# 1_P1.net
KiCad netlist of a schematic drawn in Altium Designer
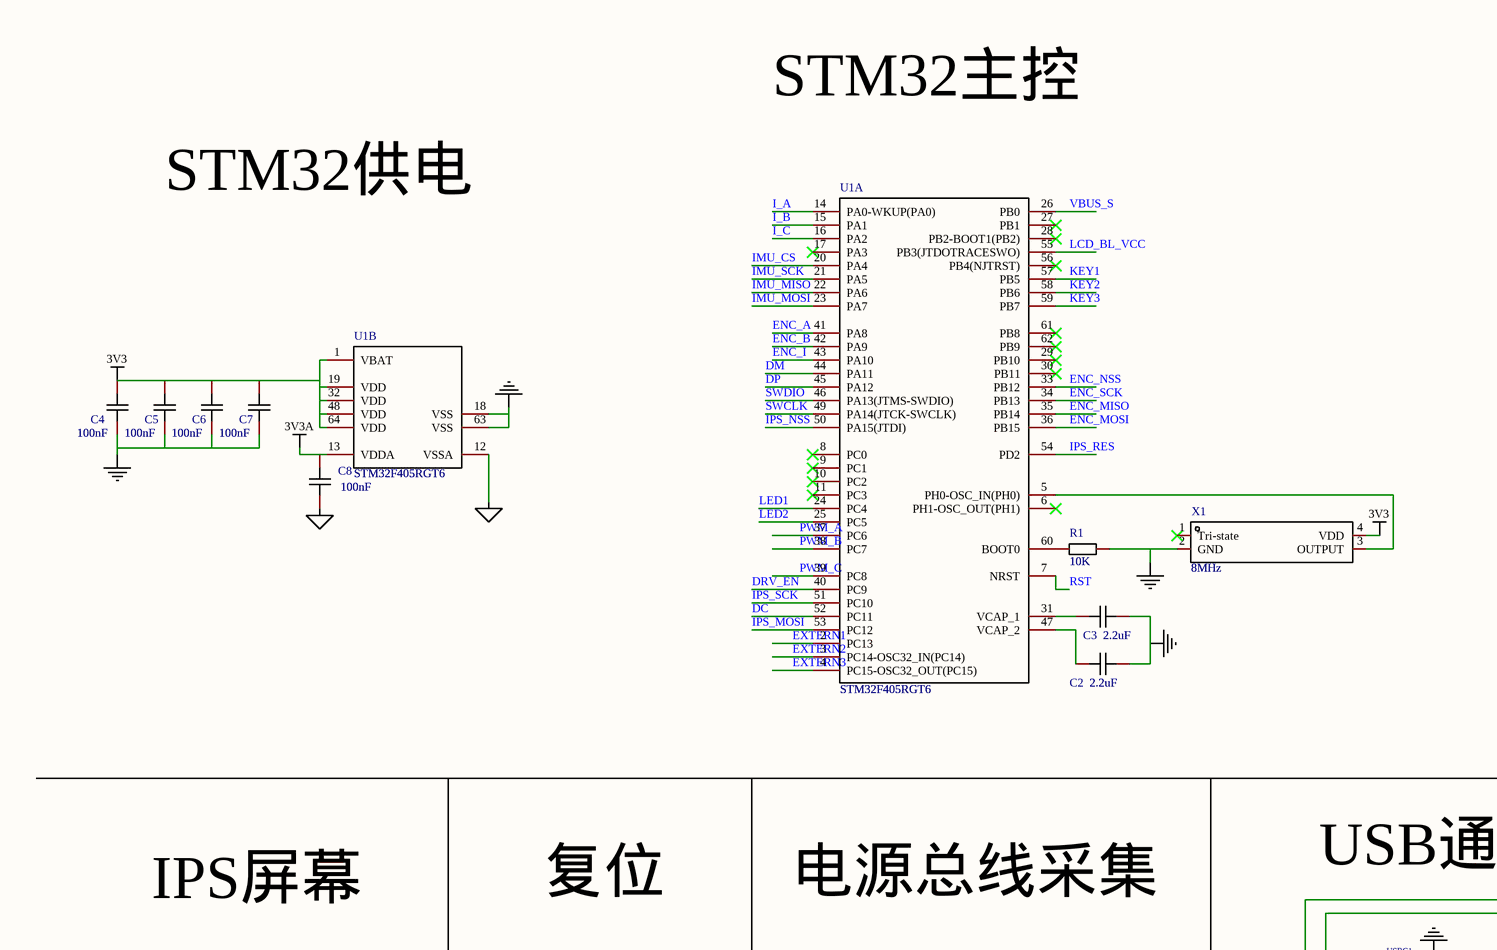
[diagram p0: 1_P1.schdoc, top left]
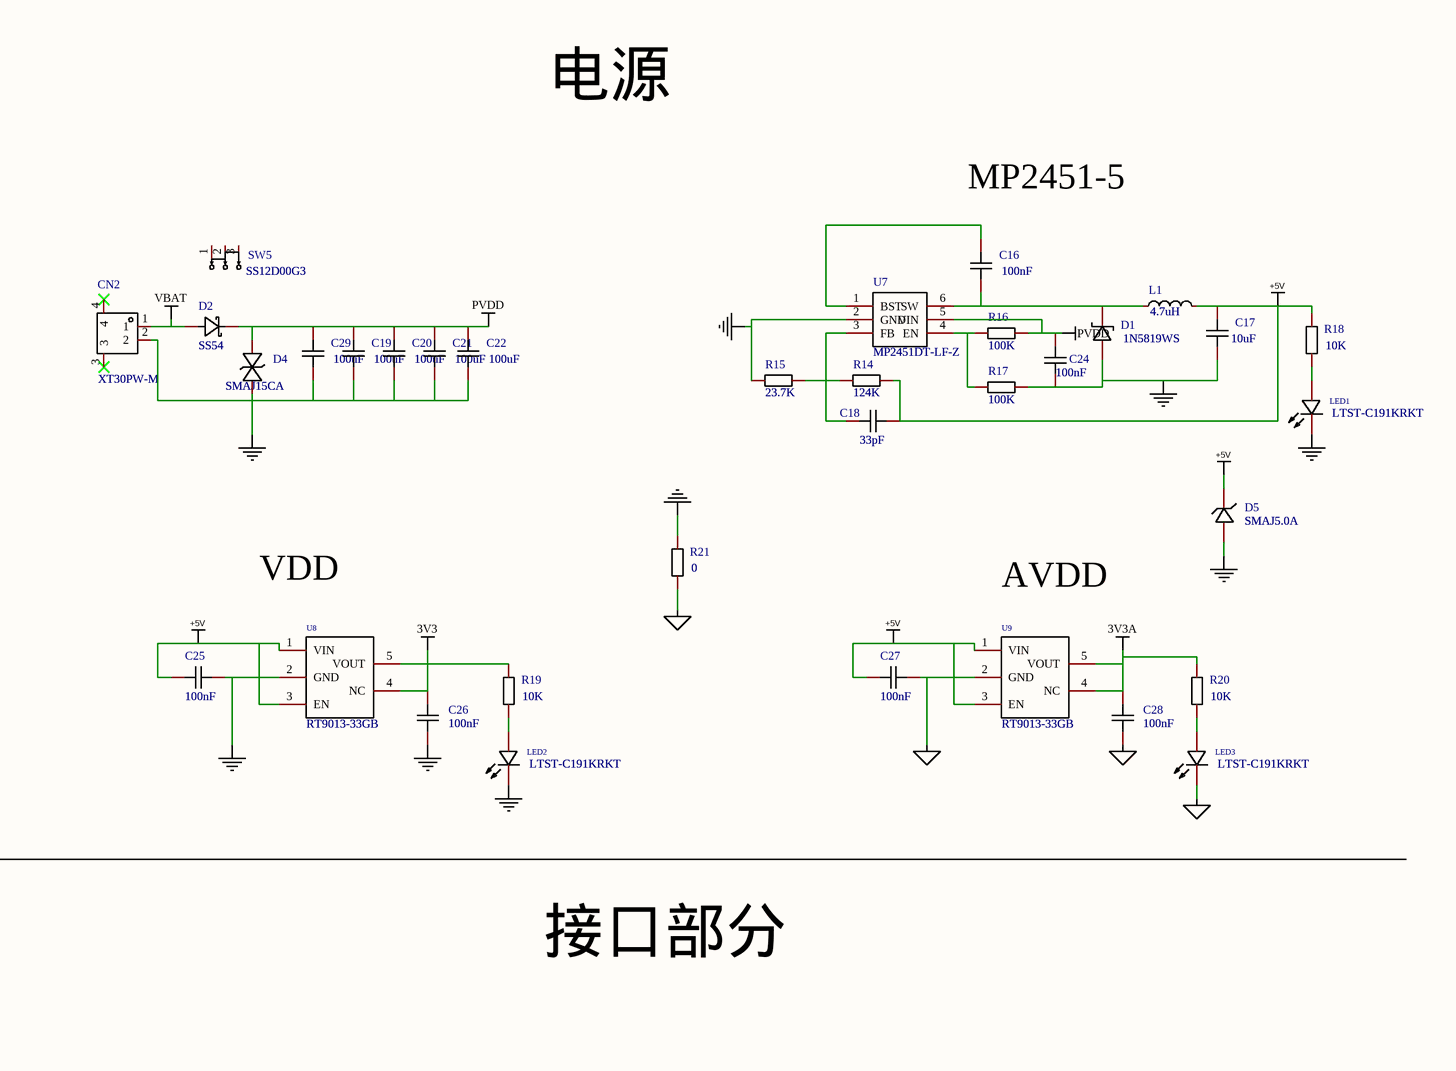
[diagram p1: 1_P1.schdoc, top right]
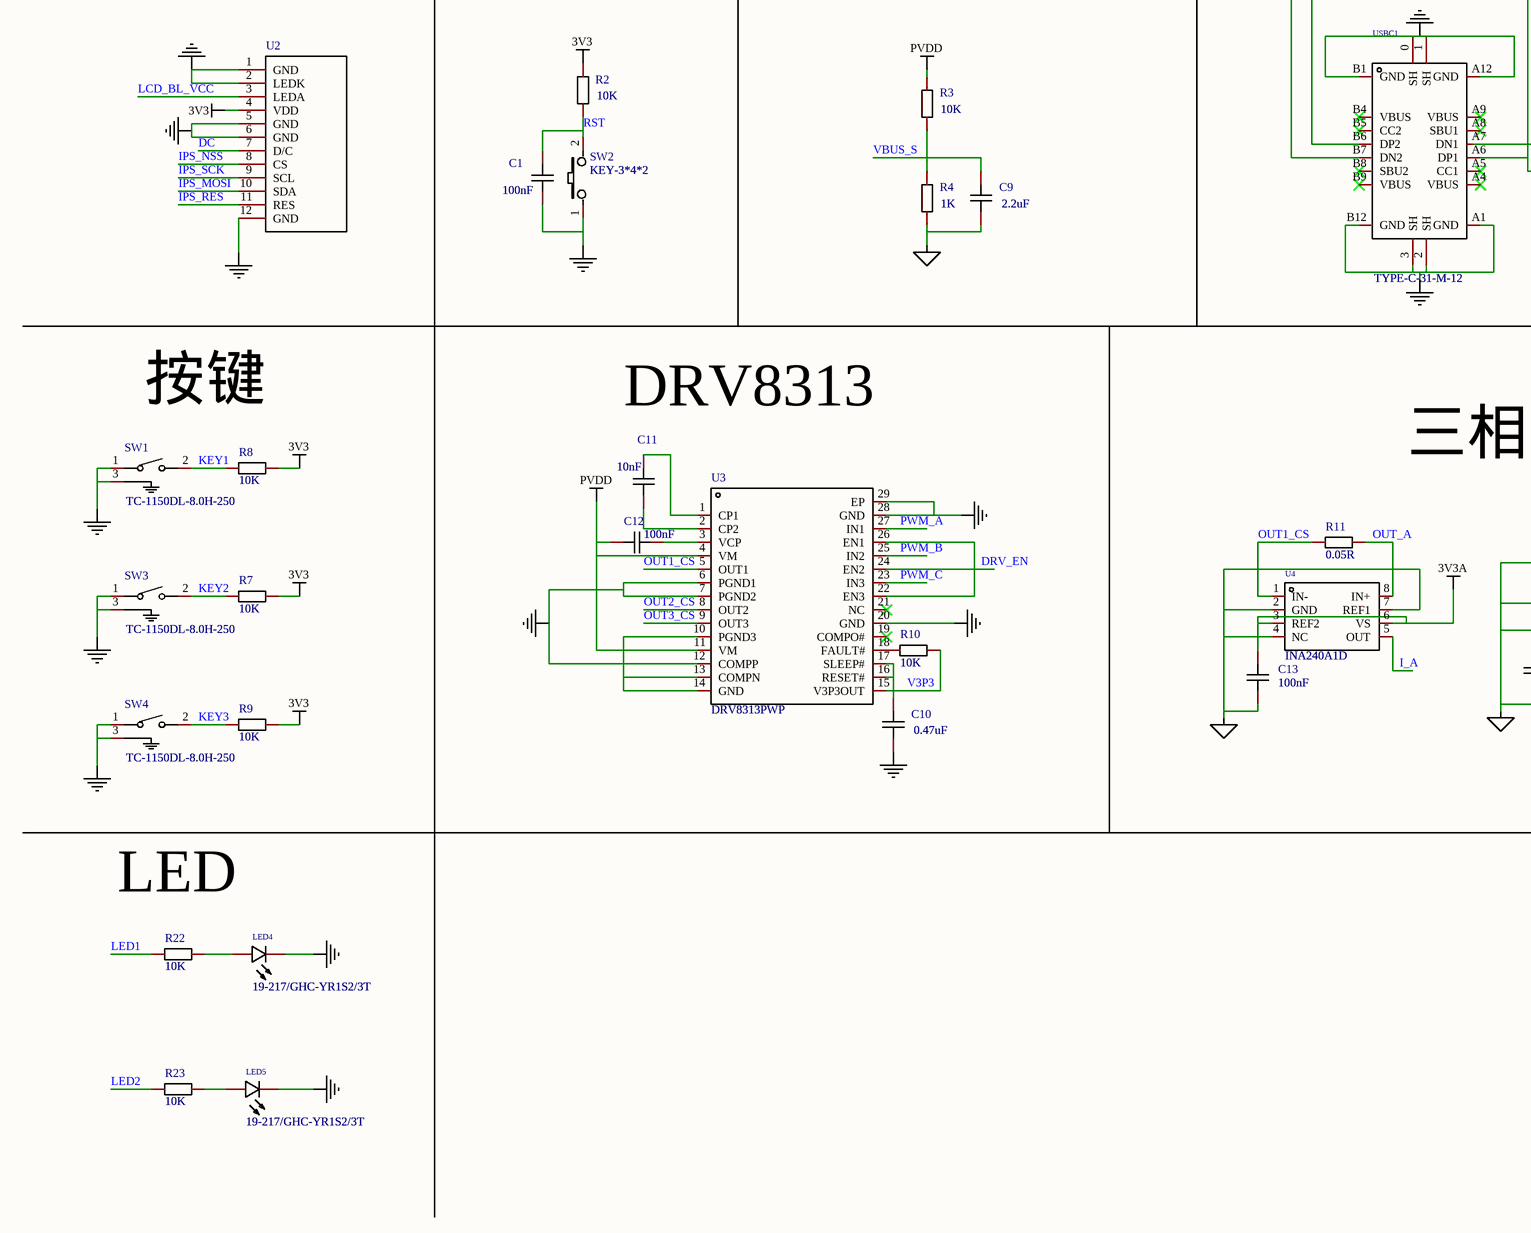
[diagram p2: 1_P1.schdoc, bottom left]
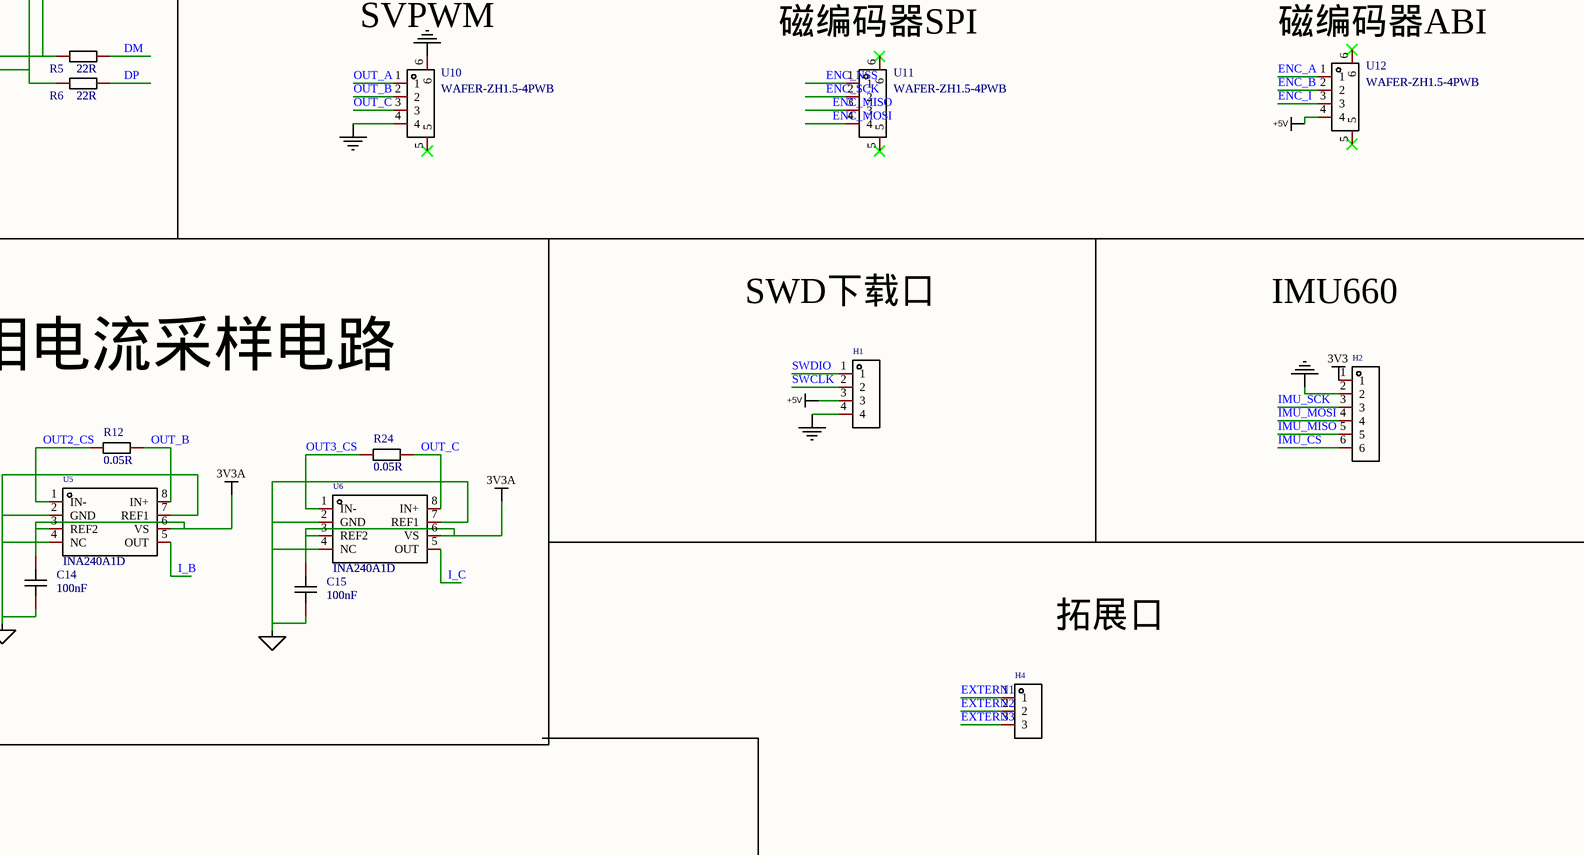
[diagram p3: 1_P1.schdoc, bottom right]

(export (version "E")
  (design (tool "Eeschema 10.0.6"))
  (components
    (comp (ref "C1")
      (value "100nF")
      (fields (field (name "NAME") "100nF"))
      (libsource (lib "altium-import") (part "root_1_CAP_0603_"))
    )
    (comp (ref "C2")
      (value "2.2uF")
      (fields (field (name "NAME") "2.2uF"))
      (libsource (lib "altium-import") (part "root_0_CAP_0603_"))
    )
    (comp (ref "C3")
      (value "2.2uF")
      (fields (field (name "NAME") "2.2uF"))
      (libsource (lib "altium-import") (part "root_0_CAP_0603_"))
    )
    (comp (ref "C4")
      (value "100nF")
      (fields (field (name "NAME") "100nF"))
      (libsource (lib "altium-import") (part "root_1_CAP_0603_"))
    )
    (comp (ref "C5")
      (value "100nF")
      (fields (field (name "NAME") "100nF"))
      (libsource (lib "altium-import") (part "root_1_CAP_0603_"))
    )
    (comp (ref "C6")
      (value "100nF")
      (fields (field (name "NAME") "100nF"))
      (libsource (lib "altium-import") (part "root_1_CAP_0603_"))
    )
    (comp (ref "C7")
      (value "100nF")
      (fields (field (name "NAME") "100nF"))
      (libsource (lib "altium-import") (part "root_1_CAP_0603_"))
    )
    (comp (ref "C8")
      (value "100nF")
      (fields (field (name "NAME") "100nF"))
      (libsource (lib "altium-import") (part "root_1_CAP_0603_"))
    )
    (comp (ref "C9")
      (value "2.2uF")
      (fields (field (name "NAME") "2.2uF"))
      (libsource (lib "altium-import") (part "root_1_CAP_0603_"))
    )
    (comp (ref "C10")
      (value "0.47uF")
      (fields (field (name "NAME") "0.47uF"))
      (libsource (lib "altium-import") (part "root_1_CAP_0603_"))
    )
    (comp (ref "C11")
      (value "10nF")
      (fields (field (name "NAME") "10nF"))
      (libsource (lib "altium-import") (part "root_1_CAP_0603_"))
    )
    (comp (ref "C12")
      (value "100nF")
      (fields (field (name "NAME") "100nF"))
      (libsource (lib "altium-import") (part "root_0_CAP_0603_"))
    )
    (comp (ref "C13")
      (value "100nF")
      (fields (field (name "NAME") "100nF"))
      (libsource (lib "altium-import") (part "root_1_CAP_0603_"))
    )
    (comp (ref "C14")
      (value "100nF")
      (fields (field (name "NAME") "100nF"))
      (libsource (lib "altium-import") (part "root_1_CAP_0603_"))
    )
    (comp (ref "C15")
      (value "100nF")
      (fields (field (name "NAME") "100nF"))
      (libsource (lib "altium-import") (part "root_1_CAP_0603_"))
    )
    (comp (ref "C16")
      (value "100nF")
      (fields (field (name "NAME") "100nF"))
      (libsource (lib "altium-import") (part "root_1_CAP_0603_"))
    )
    (comp (ref "C17")
      (value "10uF")
      (fields (field (name "NAME") "10uF"))
      (libsource (lib "altium-import") (part "root_1_CAP_0603_"))
    )
    (comp (ref "C18")
      (value "33pF")
      (fields (field (name "NAME") "33pF"))
      (libsource (lib "altium-import") (part "root_0_CAP_0603_"))
    )
    (comp (ref "C19")
      (value "100uF")
      (fields (field (name "NAME") "100uF"))
      (libsource (lib "altium-import") (part "root_1_CAP_0805_"))
    )
    (comp (ref "C20")
      (value "100uF")
      (fields (field (name "NAME") "100uF"))
      (libsource (lib "altium-import") (part "root_1_CAP_0805_"))
    )
    (comp (ref "C21")
      (value "100uF")
      (fields (field (name "NAME") "100uF"))
      (libsource (lib "altium-import") (part "root_1_CAP_0805_"))
    )
    (comp (ref "C22")
      (value "100uF")
      (fields (field (name "NAME") "100uF"))
      (libsource (lib "altium-import") (part "root_1_CAP_0805_"))
    )
    (comp (ref "C24")
      (value "100nF")
      (fields (field (name "NAME") "100nF"))
      (libsource (lib "altium-import") (part "root_1_CAP_0603_"))
    )
    (comp (ref "C25")
      (value "100nF")
      (fields (field (name "NAME") "100nF"))
      (libsource (lib "altium-import") (part "root_0_CAP_0603_"))
    )
    (comp (ref "C26")
      (value "100nF")
      (fields (field (name "NAME") "100nF"))
      (libsource (lib "altium-import") (part "root_1_CAP_0603_"))
    )
    (comp (ref "C27")
      (value "100nF")
      (fields (field (name "NAME") "100nF"))
      (libsource (lib "altium-import") (part "root_0_CAP_0603_"))
    )
    (comp (ref "C28")
      (value "100nF")
      (fields (field (name "NAME") "100nF"))
      (libsource (lib "altium-import") (part "root_1_CAP_0603_"))
    )
    (comp (ref "C29")
      (value "100uF")
      (fields (field (name "NAME") "100uF"))
      (libsource (lib "altium-import") (part "root_1_CAP_0805_"))
    )
    (comp (ref "CN2")
      (value "XT30PW-M")
      (description "Socket,DCsupply,XT30,male,PIN:2")
      (fields (field (name "NAME") "XT30PW-M") (field (name "MANUFACTURER") "AMASS(艾迈斯)"))
      (libsource (lib "altium-import") (part "root_0_mirrored_XT30PW-M_"))
    )
    (comp (ref "D1")
      (value "1N5819WS")
      (description "直流反向耐压(Vr):40V;平均整流电流(Io):1A;正向压降(Vf):600mV@1A;")
      (fields (field (name "NAME") "1N5819WS") (field (name "MANUFACTURER") "Hottech(合科泰)"))
      (libsource (lib "altium-import") (part "root_3_1N5819WS_C191023_"))
    )
    (comp (ref "D2")
      (value "SS54")
      (description "二极管配置:独立式;直流反向耐压(Vr):40V;平均整流电流(Io):5A;正向压降(Vf):550mV@5A;反向电流(Ir):500uA@40V;")
      (fields (field (name "NAME") "SS54") (field (name "MANUFACTURER") "TWGMC(台湾迪嘉)"))
      (libsource (lib "altium-import") (part "root_2_SS54_C727065_"))
    )
    (comp (ref "D4")
      (value "SMAJ15CA")
      (description "极性:双向;")
      (fields (field (name "NAME") "SMAJ15CA") (field (name "MANUFACTURER") "TWGMC(台湾迪嘉)"))
      (libsource (lib "altium-import") (part "root_1_SMAJ15CA_C726784_"))
    )
    (comp (ref "D5")
      (value "SMAJ5.0A")
      (description "极性:单向;反向截止电压(Vrwm):5V;击穿电压:6.4V;反向漏电流(Ir):800uA;峰值脉冲电流(Ipp)@10/1000s:43.5A;最大钳位电压:9.2V;")
      (fields (field (name "NAME") "SMAJ5.0A") (field (name "MANUFACTURER") "MDD"))
      (libsource (lib "altium-import") (part "root_3_SMAJ5.0A_C113952_"))
    )
    (comp (ref "H1")
      (value "HDR-F_2.54_1x4P")
      (fields (field (name "MANUFACTURER") "BOOMELE(博穆精密)") (field (name "MANUFACTURER PART") "2.54-1*4P母"))
      (libsource (lib "altium-import") (part "root_0_HDR-F_2.54_1x4P_"))
    )
    (comp (ref "H2")
      (value "HDR-F_2.54_1x6P")
      (fields (field (name "MANUFACTURER") "BOOMELE(博穆精密)") (field (name "MANUFACTURER PART") "2.54-1*6P母"))
      (libsource (lib "altium-import") (part "root_0_HDR-F_2.54_1x6P_"))
    )
    (comp (ref "H4")
      (value "HDR-F_2.54_1x3P")
      (fields (field (name "MANUFACTURER") "XFCN(兴飞)") (field (name "MANUFACTURER PART") "PM254V-11-03-H85"))
      (libsource (lib "altium-import") (part "root_0_HDR-F_2.54_1x3P_"))
    )
    (comp (ref "L1")
      (value "4.7uH")
      (description "电感值:4.7uH;精度:±20%;额定电流:3.2A;")
      (fields
        (field (name "NAME") "4.7uH")
        (field (name "MANUFACTURER") "Gantong(感通)")
        (field (name "MANUFACTURER PART") "GPSR0520-4R7M")
      )
      (libsource (lib "altium-import") (part "root_0_GPSR0520-4R7M_"))
    )
    (comp (ref "LED1")
      (value "LTST-C191KRKT")
      (description "发光颜色:红灯;二极管配置:-;透镜颜色:无色透明;主波长:631nm;色温:-;功率:75mW;发光角度:130°;安装方式:-;工作温度:-55℃~+85℃;")
      (fields (field (name "NAME") "LTST-C191KRKT") (field (name "MANUFACTURER") "LITEON(光宝)"))
      (libsource (lib "altium-import") (part "root_1_LTST-C191KRKT_"))
    )
    (comp (ref "LED2")
      (value "LTST-C191KRKT")
      (description "发光颜色:红灯;二极管配置:-;透镜颜色:无色透明;主波长:631nm;色温:-;功率:75mW;发光角度:130°;安装方式:-;工作温度:-55℃~+85℃;")
      (fields (field (name "NAME") "LTST-C191KRKT") (field (name "MANUFACTURER") "LITEON(光宝)"))
      (libsource (lib "altium-import") (part "root_1_LTST-C191KRKT_"))
    )
    (comp (ref "LED3")
      (value "LTST-C191KRKT")
      (description "发光颜色:红灯;二极管配置:-;透镜颜色:无色透明;主波长:631nm;色温:-;功率:75mW;发光角度:130°;安装方式:-;工作温度:-55℃~+85℃;")
      (fields (field (name "NAME") "LTST-C191KRKT") (field (name "MANUFACTURER") "LITEON(光宝)"))
      (libsource (lib "altium-import") (part "root_1_LTST-C191KRKT_"))
    )
    (comp (ref "LED4")
      (value "19-217/GHC-YR1S2/3T")
      (description "发光颜色:翠绿;二极管配置:-;主波长:520nm~535nm;色温:-;功率:110mW;安装方式:-;")
      (fields (field (name "NAME") "19-217/GHC-YR1S2/3T") (field (name "MANUFACTURER") "EVERLIGHT(亿光)"))
      (libsource (lib "altium-import") (part "root_2_19-217/GHC-YR1S2/3T_"))
    )
    (comp (ref "LED5")
      (value "19-217/GHC-YR1S2/3T")
      (description "发光颜色:翠绿;二极管配置:-;主波长:520nm~535nm;色温:-;功率:110mW;安装方式:-;")
      (fields (field (name "NAME") "19-217/GHC-YR1S2/3T") (field (name "MANUFACTURER") "EVERLIGHT(亿光)"))
      (libsource (lib "altium-import") (part "root_2_19-217/GHC-YR1S2/3T_"))
    )
    (comp (ref "R1")
      (value "10K")
      (fields (field (name "NAME") "10K"))
      (libsource (lib "altium-import") (part "root_0_Res_0603_"))
    )
    (comp (ref "R2")
      (value "10K")
      (fields (field (name "NAME") "10K"))
      (libsource (lib "altium-import") (part "root_1_Res_0603_"))
    )
    (comp (ref "R3")
      (value "10K")
      (fields (field (name "NAME") "10K"))
      (libsource (lib "altium-import") (part "root_1_Res_0603_"))
    )
    (comp (ref "R4")
      (value "1K")
      (fields (field (name "NAME") "1K"))
      (libsource (lib "altium-import") (part "root_1_Res_0603_"))
    )
    (comp (ref "R5")
      (value "22R")
      (fields (field (name "NAME") "22R"))
      (libsource (lib "altium-import") (part "root_0_Res_0603_"))
    )
    (comp (ref "R6")
      (value "22R")
      (fields (field (name "NAME") "22R"))
      (libsource (lib "altium-import") (part "root_0_Res_0603_"))
    )
    (comp (ref "R7")
      (value "10K")
      (fields (field (name "NAME") "10K"))
      (libsource (lib "altium-import") (part "root_0_Res_0603_"))
    )
    (comp (ref "R8")
      (value "10K")
      (fields (field (name "NAME") "10K"))
      (libsource (lib "altium-import") (part "root_0_Res_0603_"))
    )
    (comp (ref "R9")
      (value "10K")
      (fields (field (name "NAME") "10K"))
      (libsource (lib "altium-import") (part "root_0_Res_0603_"))
    )
    (comp (ref "R10")
      (value "10K")
      (fields (field (name "NAME") "10K"))
      (libsource (lib "altium-import") (part "root_0_Res_0603_"))
    )
    (comp (ref "R11")
      (value "0.05R")
      (fields (field (name "NAME") "0.05R"))
      (libsource (lib "altium-import") (part "root_0_Res_0805_"))
    )
    (comp (ref "R12")
      (value "0.05R")
      (fields (field (name "NAME") "0.05R"))
      (libsource (lib "altium-import") (part "root_0_Res_0805_"))
    )
    (comp (ref "R14")
      (value "124K")
      (fields (field (name "NAME") "124K"))
      (libsource (lib "altium-import") (part "root_0_Res_0603_"))
    )
    (comp (ref "R15")
      (value "23.7K")
      (fields (field (name "NAME") "23.7K"))
      (libsource (lib "altium-import") (part "root_0_Res_0603_"))
    )
    (comp (ref "R16")
      (value "100K")
      (fields (field (name "NAME") "100K"))
      (libsource (lib "altium-import") (part "root_0_Res_0603_"))
    )
    (comp (ref "R17")
      (value "100K")
      (fields (field (name "NAME") "100K"))
      (libsource (lib "altium-import") (part "root_0_Res_0603_"))
    )
    (comp (ref "R18")
      (value "10K")
      (fields (field (name "NAME") "10K"))
      (libsource (lib "altium-import") (part "root_1_Res_0603_"))
    )
    (comp (ref "R19")
      (value "10K")
      (fields (field (name "NAME") "10K"))
      (libsource (lib "altium-import") (part "root_1_Res_0603_"))
    )
    (comp (ref "R20")
      (value "10K")
      (fields (field (name "NAME") "10K"))
      (libsource (lib "altium-import") (part "root_1_Res_0603_"))
    )
    (comp (ref "R21")
      (value "0")
      (fields (field (name "NAME") "0"))
      (libsource (lib "altium-import") (part "root_1_Res_0603_"))
    )
    (comp (ref "R22")
      (value "10K")
      (fields (field (name "NAME") "10K"))
      (libsource (lib "altium-import") (part "root_0_Res_0603_"))
    )
    (comp (ref "R23")
      (value "10K")
      (fields (field (name "NAME") "10K"))
      (libsource (lib "altium-import") (part "root_0_Res_0603_"))
    )
    (comp (ref "R24")
      (value "0.05R")
      (fields (field (name "NAME") "0.05R"))
      (libsource (lib "altium-import") (part "root_0_Res_0805_"))
    )
    (comp (ref "SW1")
      (value "TC-1150DL-8.0H-250")
      (description "电路结构:单刀单掷;安装方式:卧插;作用力:250gf@±50gf;机械寿命:-;带支架:否;")
      (fields (field (name "NAME") "TC-1150DL-8.0H-250") (field (name "MANUFACTURER") "DEALON(德艺隆)"))
      (libsource (lib "altium-import") (part "root_0_TC-1150DL-8.0H-250_"))
    )
    (comp (ref "SW2")
      (value "KEY-3*4*2")
      (fields (field (name "NAME") "KEY-3*4*2"))
      (libsource (lib "altium-import") (part "root_1_KEY-3*4*2_"))
    )
    (comp (ref "SW3")
      (value "TC-1150DL-8.0H-250")
      (description "电路结构:单刀单掷;安装方式:卧插;作用力:250gf@±50gf;机械寿命:-;带支架:否;")
      (fields (field (name "NAME") "TC-1150DL-8.0H-250") (field (name "MANUFACTURER") "DEALON(德艺隆)"))
      (libsource (lib "altium-import") (part "root_0_TC-1150DL-8.0H-250_"))
    )
    (comp (ref "SW4")
      (value "TC-1150DL-8.0H-250")
      (description "电路结构:单刀单掷;安装方式:卧插;作用力:250gf@±50gf;机械寿命:-;带支架:否;")
      (fields (field (name "NAME") "TC-1150DL-8.0H-250") (field (name "MANUFACTURER") "DEALON(德艺隆)"))
      (libsource (lib "altium-import") (part "root_0_TC-1150DL-8.0H-250_"))
    )
    (comp (ref "SW5")
      (value "SS12D00G3")
      (fields (field (name "NAME") "SS12D00G3"))
      (libsource (lib "altium-import") (part "root_0_SS12D00G3_"))
    )
    (comp (ref "U1")
      (value "STM32F405RGT6")
      (description "CPU内核:ARM Cortex-M4;CPU最大主频:168MHz;程序存储容量:1MB;程序存储器类型:FLASH;RAM总容量:192KB;GPIO端口数量:51;")
      (fields (field (name "NAME") "STM32F405RGT6") (field (name "MANUFACTURER") "ST(意法半导体)"))
      (libsource (lib "altium-import") (part "root_0_STM32F405RGT6_"))
    )
    (comp (ref "U2") (value "IPS-12P") (libsource (lib "altium-import") (part "root_0_IPS-12P_")))
    (comp (ref "U3")
      (value "DRV8313PWP")
      (description "最大电压为 65V 的 3A 峰值三相电机驱动器 28-HTSSOP -40 to 125")
      (fields (field (name "NAME") "DRV8313PWP") (field (name "MANUFACTURER") "TI(德州仪器)"))
      (libsource (lib "altium-import") (part "root_0_DRV8313PWP_"))
    )
    (comp (ref "U4")
      (value "INA240A1D")
      (description "通道数:1;")
      (fields (field (name "NAME") "INA240A1D") (field (name "MANUFACTURER") "TI(德州仪器)"))
      (libsource (lib "altium-import") (part "root_0_INA240A1D_"))
    )
    (comp (ref "U5")
      (value "INA240A1D")
      (description "通道数:1;")
      (fields (field (name "NAME") "INA240A1D") (field (name "MANUFACTURER") "TI(德州仪器)"))
      (libsource (lib "altium-import") (part "root_0_INA240A1D_"))
    )
    (comp (ref "U6")
      (value "INA240A1D")
      (description "通道数:1;")
      (fields (field (name "NAME") "INA240A1D") (field (name "MANUFACTURER") "TI(德州仪器)"))
      (libsource (lib "altium-import") (part "root_0_INA240A1D_"))
    )
    (comp (ref "U7")
      (value "MP2451DT-LF-Z")
      (description "最大输入电压:-;可输出电流:-;")
      (fields (field (name "NAME") "MP2451DT-LF-Z"))
      (libsource (lib "altium-import") (part "root_0_MP2451DT-LF-Z_"))
    )
    (comp (ref "U8")
      (value "RT9013-33GB")
      (description "输出类型:固定;输出极性:正;最大输入电压:5.5V;输出电压:3.3V;输出电流:500mA;电源纹波抑制比(PSRR):50dB@(10kHz);")
      (fields (field (name "NAME") "RT9013-33GB") (field (name "MANUFACTURER") "RICHTEK(立锜)"))
      (libsource (lib "altium-import") (part "root_0_RT9013-33GB_"))
    )
    (comp (ref "U9")
      (value "RT9013-33GB")
      (description "输出类型:固定;输出极性:正;最大输入电压:5.5V;输出电压:3.3V;输出电流:500mA;电源纹波抑制比(PSRR):50dB@(10kHz);")
      (fields (field (name "NAME") "RT9013-33GB") (field (name "MANUFACTURER") "RICHTEK(立锜)"))
      (libsource (lib "altium-import") (part "root_0_RT9013-33GB_"))
    )
    (comp (ref "U10")
      (value "WAFER-ZH1.5-4PWB")
      (fields (field (name "NAME") "WAFER-ZH1.5-4PWB") (field (name "MANUFACTURER") "XUNPU(讯普)"))
      (libsource (lib "altium-import") (part "root_0_WAFER-ZH1.5-4PWB_"))
    )
    (comp (ref "U11")
      (value "WAFER-ZH1.5-4PWB")
      (fields (field (name "NAME") "WAFER-ZH1.5-4PWB") (field (name "MANUFACTURER") "XUNPU(讯普)"))
      (libsource (lib "altium-import") (part "root_0_WAFER-ZH1.5-4PWB_"))
    )
    (comp (ref "U12")
      (value "WAFER-ZH1.5-4PWB")
      (fields (field (name "NAME") "WAFER-ZH1.5-4PWB") (field (name "MANUFACTURER") "XUNPU(讯普)"))
      (libsource (lib "altium-import") (part "root_0_WAFER-ZH1.5-4PWB_"))
    )
    (comp (ref "USBC1")
      (value "TYPE-C-31-M-12")
      (description "连接器类型:Type-C;标准:-;公母:母座;触点数量:16P;端口数量:1;安装方式:-;额定电流 - 电源:5A;触头材质:-;触头镀层:-;工作温度范围:-;焊接温度(最大值):-;")
      (fields (field (name "NAME") "TYPE-C-31-M-12") (field (name "MANUFACTURER") "韩国韩荣"))
      (libsource (lib "altium-import") (part "root_0_TYPE-C-31-M-12_"))
    )
    (comp (ref "X1")
      (value "8MHz")
      (description "频率:8MHz;频率稳定度:±10ppm;工作电压:1.8V~3.3V;")
      (fields
        (field (name "NAME") "8MHz")
        (field (name "MANUFACTURER") "YXC(扬兴晶振)")
        (field (name "MANUFACTURER PART") "OT32258MJBA4SL")
      )
      (libsource (lib "altium-import") (part "root_0_OT32258MJBA4SL_"))
    )
  )
  (nets
    (net (code "1") (name "+5V") (class "Default")
      (node (ref "C17") (pin "2") (pinfunction "2_2") (pintype "passive"))
      (node (ref "C18") (pin "2") (pinfunction "2_2") (pintype "passive"))
      (node (ref "C25") (pin "1") (pinfunction "1_1") (pintype "passive"))
      (node (ref "C27") (pin "1") (pinfunction "1_1") (pintype "passive"))
      (node (ref "D5") (pin "1") (pinfunction "1_1") (pintype "passive"))
      (node (ref "H1") (pin "3") (pinfunction "3_3") (pintype "passive"))
      (node (ref "L1") (pin "2") (pinfunction "2_2") (pintype "passive"))
      (node (ref "R14") (pin "2") (pinfunction "2_2") (pintype "passive"))
      (node (ref "R18") (pin "2") (pinfunction "2_2") (pintype "passive"))
      (node (ref "U12") (pin "4") (pinfunction "4_4") (pintype "passive"))
      (node (ref "U8") (pin "1") (pinfunction "VIN_1") (pintype "passive"))
      (node (ref "U8") (pin "3") (pinfunction "EN_3") (pintype "passive"))
      (node (ref "U9") (pin "1") (pinfunction "VIN_1") (pintype "passive"))
      (node (ref "U9") (pin "3") (pinfunction "EN_3") (pintype "passive"))
    )
    (net (code "2") (name "/DC") (class "Default")
      (node (ref "U1") (pin "52") (pinfunction "PC11_52") (pintype "passive"))
      (node (ref "U2") (pin "7") (pinfunction "D/C_7") (pintype "passive"))
    )
    (net (code "3") (name "/DM") (class "Default")
      (node (ref "R5") (pin "2") (pinfunction "2_2") (pintype "passive"))
      (node (ref "U1") (pin "44") (pinfunction "PA11_44") (pintype "passive"))
    )
    (net (code "4") (name "/DP") (class "Default")
      (node (ref "R6") (pin "2") (pinfunction "2_2") (pintype "passive"))
      (node (ref "U1") (pin "45") (pinfunction "PA12_45") (pintype "passive"))
    )
    (net (code "5") (name "/DRV_EN") (class "Default")
      (node (ref "U1") (pin "40") (pinfunction "PC9_40") (pintype "passive"))
      (node (ref "U3") (pin "22") (pinfunction "EN3_22") (pintype "passive"))
      (node (ref "U3") (pin "24") (pinfunction "EN2_24") (pintype "passive"))
      (node (ref "U3") (pin "26") (pinfunction "EN1_26") (pintype "passive"))
    )
    (net (code "6") (name "/ENC_A") (class "Default")
      (node (ref "U1") (pin "41") (pinfunction "PA8_41") (pintype "passive"))
      (node (ref "U12") (pin "1") (pinfunction "1_1") (pintype "passive"))
    )
    (net (code "7") (name "/ENC_B") (class "Default")
      (node (ref "U1") (pin "42") (pinfunction "PA9_42") (pintype "passive"))
      (node (ref "U12") (pin "2") (pinfunction "2_2") (pintype "passive"))
    )
    (net (code "8") (name "/ENC_I") (class "Default")
      (node (ref "U1") (pin "43") (pinfunction "PA10_43") (pintype "passive"))
      (node (ref "U12") (pin "3") (pinfunction "3_3") (pintype "passive"))
    )
    (net (code "9") (name "/ENC_MISO") (class "Default")
      (node (ref "U1") (pin "35") (pinfunction "PB14_35") (pintype "passive"))
      (node (ref "U11") (pin "3") (pinfunction "3_3") (pintype "passive"))
    )
    (net (code "10") (name "/ENC_MOSI") (class "Default")
      (node (ref "U1") (pin "36") (pinfunction "PB15_36") (pintype "passive"))
      (node (ref "U11") (pin "4") (pinfunction "4_4") (pintype "passive"))
    )
    (net (code "11") (name "/ENC_NSS") (class "Default")
      (node (ref "U1") (pin "33") (pinfunction "PB12_33") (pintype "passive"))
      (node (ref "U11") (pin "1") (pinfunction "1_1") (pintype "passive"))
    )
    (net (code "12") (name "/ENC_SCK") (class "Default")
      (node (ref "U1") (pin "34") (pinfunction "PB13_34") (pintype "passive"))
      (node (ref "U11") (pin "2") (pinfunction "2_2") (pintype "passive"))
    )
    (net (code "13") (name "/EXTERN1") (class "Default")
      (node (ref "H4") (pin "1") (pinfunction "1_1") (pintype "passive"))
      (node (ref "U1") (pin "2") (pinfunction "PC13_2") (pintype "passive"))
    )
    (net (code "14") (name "/EXTERN2") (class "Default")
      (node (ref "H4") (pin "2") (pinfunction "2_2") (pintype "passive"))
      (node (ref "U1") (pin "3") (pinfunction "PC14-OSC32_IN(PC14)_3") (pintype "passive"))
    )
    (net (code "15") (name "/EXTERN3") (class "Default")
      (node (ref "H4") (pin "3") (pinfunction "3_3") (pintype "passive"))
      (node (ref "U1") (pin "4") (pinfunction "PC15-OSC32_OUT(PC15)_4") (pintype "passive"))
    )
    (net (code "16") (name "/IMU_CS") (class "Default")
      (node (ref "H2") (pin "6") (pinfunction "6_6") (pintype "passive"))
      (node (ref "U1") (pin "20") (pinfunction "PA4_20") (pintype "passive"))
    )
    (net (code "17") (name "/IMU_MISO") (class "Default")
      (node (ref "H2") (pin "5") (pinfunction "5_5") (pintype "passive"))
      (node (ref "U1") (pin "22") (pinfunction "PA6_22") (pintype "passive"))
    )
    (net (code "18") (name "/IMU_MOSI") (class "Default")
      (node (ref "H2") (pin "4") (pinfunction "4_4") (pintype "passive"))
      (node (ref "U1") (pin "23") (pinfunction "PA7_23") (pintype "passive"))
    )
    (net (code "19") (name "/IMU_SCK") (class "Default")
      (node (ref "H2") (pin "3") (pinfunction "3_3") (pintype "passive"))
      (node (ref "U1") (pin "21") (pinfunction "PA5_21") (pintype "passive"))
    )
    (net (code "20") (name "/IPS_MOSI") (class "Default")
      (node (ref "U1") (pin "53") (pinfunction "PC12_53") (pintype "passive"))
      (node (ref "U2") (pin "10") (pinfunction "SDA_10") (pintype "passive"))
    )
    (net (code "21") (name "/IPS_NSS") (class "Default")
      (node (ref "U1") (pin "50") (pinfunction "PA15(JTDI)_50") (pintype "passive"))
      (node (ref "U2") (pin "8") (pinfunction "CS_8") (pintype "passive"))
    )
    (net (code "22") (name "/IPS_RES") (class "Default")
      (node (ref "U1") (pin "54") (pinfunction "PD2_54") (pintype "passive"))
      (node (ref "U2") (pin "11") (pinfunction "RES_11") (pintype "passive"))
    )
    (net (code "23") (name "/IPS_SCK") (class "Default")
      (node (ref "U1") (pin "51") (pinfunction "PC10_51") (pintype "passive"))
      (node (ref "U2") (pin "9") (pinfunction "SCL_9") (pintype "passive"))
    )
    (net (code "24") (name "/I_A") (class "Default")
      (node (ref "U1") (pin "14") (pinfunction "PA0-WKUP(PA0)_14") (pintype "passive"))
      (node (ref "U4") (pin "5") (pinfunction "OUT_5") (pintype "passive"))
    )
    (net (code "25") (name "/I_B") (class "Default")
      (node (ref "U1") (pin "15") (pinfunction "PA1_15") (pintype "passive"))
      (node (ref "U5") (pin "5") (pinfunction "OUT_5") (pintype "passive"))
    )
    (net (code "26") (name "/I_C") (class "Default")
      (node (ref "U1") (pin "16") (pinfunction "PA2_16") (pintype "passive"))
      (node (ref "U6") (pin "5") (pinfunction "OUT_5") (pintype "passive"))
    )
    (net (code "27") (name "/KEY1") (class "Default")
      (node (ref "R8") (pin "1") (pinfunction "1_1") (pintype "passive"))
      (node (ref "SW1") (pin "2") (pinfunction "2_2") (pintype "passive"))
      (node (ref "U1") (pin "57") (pinfunction "PB5_57") (pintype "passive"))
    )
    (net (code "28") (name "/KEY2") (class "Default")
      (node (ref "R7") (pin "1") (pinfunction "1_1") (pintype "passive"))
      (node (ref "SW3") (pin "2") (pinfunction "2_2") (pintype "passive"))
      (node (ref "U1") (pin "58") (pinfunction "PB6_58") (pintype "passive"))
    )
    (net (code "29") (name "/KEY3") (class "Default")
      (node (ref "R9") (pin "1") (pinfunction "1_1") (pintype "passive"))
      (node (ref "SW4") (pin "2") (pinfunction "2_2") (pintype "passive"))
      (node (ref "U1") (pin "59") (pinfunction "PB7_59") (pintype "passive"))
    )
    (net (code "30") (name "/LCD_BL_VCC") (class "Default")
      (node (ref "U1") (pin "55") (pinfunction "PB3(JTDOTRACESWO)_55") (pintype "passive"))
      (node (ref "U2") (pin "3") (pinfunction "LEDA_3") (pintype "passive"))
    )
    (net (code "31") (name "/LED1") (class "Default")
      (node (ref "R22") (pin "1") (pinfunction "1_1") (pintype "passive"))
      (node (ref "U1") (pin "24") (pinfunction "PC4_24") (pintype "passive"))
    )
    (net (code "32") (name "/LED2") (class "Default")
      (node (ref "R23") (pin "1") (pinfunction "1_1") (pintype "passive"))
      (node (ref "U1") (pin "25") (pinfunction "PC5_25") (pintype "passive"))
    )
    (net (code "33") (name "/OUT1_CS") (class "Default")
      (node (ref "R11") (pin "1") (pinfunction "1_1") (pintype "passive"))
      (node (ref "U3") (pin "5") (pinfunction "OUT1_5") (pintype "passive"))
      (node (ref "U4") (pin "1") (pinfunction "IN-_1") (pintype "passive"))
    )
    (net (code "34") (name "/OUT2_CS") (class "Default")
      (node (ref "R12") (pin "1") (pinfunction "1_1") (pintype "passive"))
      (node (ref "U3") (pin "8") (pinfunction "OUT2_8") (pintype "passive"))
      (node (ref "U5") (pin "1") (pinfunction "IN-_1") (pintype "passive"))
    )
    (net (code "35") (name "/OUT3_CS") (class "Default")
      (node (ref "R24") (pin "1") (pinfunction "1_1") (pintype "passive"))
      (node (ref "U3") (pin "9") (pinfunction "OUT3_9") (pintype "passive"))
      (node (ref "U6") (pin "1") (pinfunction "IN-_1") (pintype "passive"))
    )
    (net (code "36") (name "/OUT_A") (class "Default")
      (node (ref "R11") (pin "2") (pinfunction "2_2") (pintype "passive"))
      (node (ref "U10") (pin "1") (pinfunction "1_1") (pintype "passive"))
      (node (ref "U4") (pin "8") (pinfunction "IN+_8") (pintype "passive"))
    )
    (net (code "37") (name "/OUT_B") (class "Default")
      (node (ref "R12") (pin "2") (pinfunction "2_2") (pintype "passive"))
      (node (ref "U10") (pin "2") (pinfunction "2_2") (pintype "passive"))
      (node (ref "U5") (pin "8") (pinfunction "IN+_8") (pintype "passive"))
    )
    (net (code "38") (name "/OUT_C") (class "Default")
      (node (ref "R24") (pin "2") (pinfunction "2_2") (pintype "passive"))
      (node (ref "U10") (pin "3") (pinfunction "3_3") (pintype "passive"))
      (node (ref "U6") (pin "8") (pinfunction "IN+_8") (pintype "passive"))
    )
    (net (code "39") (name "/PWM_A") (class "Default")
      (node (ref "U1") (pin "37") (pinfunction "PC6_37") (pintype "passive"))
      (node (ref "U3") (pin "27") (pinfunction "IN1_27") (pintype "passive"))
    )
    (net (code "40") (name "/PWM_B") (class "Default")
      (node (ref "U1") (pin "38") (pinfunction "PC7_38") (pintype "passive"))
      (node (ref "U3") (pin "25") (pinfunction "IN2_25") (pintype "passive"))
    )
    (net (code "41") (name "/PWM_C") (class "Default")
      (node (ref "U1") (pin "39") (pinfunction "PC8_39") (pintype "passive"))
      (node (ref "U3") (pin "23") (pinfunction "IN3_23") (pintype "passive"))
    )
    (net (code "42") (name "/RST") (class "Default")
      (node (ref "C1") (pin "2") (pinfunction "2_2") (pintype "passive"))
      (node (ref "R2") (pin "1") (pinfunction "1_1") (pintype "passive"))
      (node (ref "SW2") (pin "2") (pinfunction "2_2") (pintype "passive"))
      (node (ref "U1") (pin "7") (pinfunction "NRST_7") (pintype "passive"))
    )
    (net (code "43") (name "/SWCLK") (class "Default")
      (node (ref "H1") (pin "2") (pinfunction "2_2") (pintype "passive"))
      (node (ref "U1") (pin "49") (pinfunction "PA14(JTCK-SWCLK)_49") (pintype "passive"))
    )
    (net (code "44") (name "/SWDIO") (class "Default")
      (node (ref "H1") (pin "1") (pinfunction "1_1") (pintype "passive"))
      (node (ref "U1") (pin "46") (pinfunction "PA13(JTMS-SWDIO)_46") (pintype "passive"))
    )
    (net (code "45") (name "/V3P3") (class "Default")
      (node (ref "C10") (pin "2") (pinfunction "2_2") (pintype "passive"))
      (node (ref "R10") (pin "2") (pinfunction "2_2") (pintype "passive"))
      (node (ref "U3") (pin "15") (pinfunction "V3P3OUT_15") (pintype "passive"))
      (node (ref "U3") (pin "16") (pinfunction "RESET#_16") (pintype "passive"))
      (node (ref "U3") (pin "17") (pinfunction "SLEEP#_17") (pintype "passive"))
    )
    (net (code "46") (name "/VBUS_S") (class "Default")
      (node (ref "C9") (pin "2") (pinfunction "2_2") (pintype "passive"))
      (node (ref "R3") (pin "1") (pinfunction "1_1") (pintype "passive"))
      (node (ref "R4") (pin "2") (pinfunction "2_2") (pintype "passive"))
      (node (ref "U1") (pin "26") (pinfunction "PB0_26") (pintype "passive"))
    )
    (net (code "47") (name "3V3") (class "Default")
      (node (ref "C26") (pin "2") (pinfunction "2_2") (pintype "passive"))
      (node (ref "C4") (pin "2") (pinfunction "2_2") (pintype "passive"))
      (node (ref "C5") (pin "2") (pinfunction "2_2") (pintype "passive"))
      (node (ref "C6") (pin "2") (pinfunction "2_2") (pintype "passive"))
      (node (ref "C7") (pin "2") (pinfunction "2_2") (pintype "passive"))
      (node (ref "H2") (pin "1") (pinfunction "1_1") (pintype "passive"))
      (node (ref "R19") (pin "2") (pinfunction "2_2") (pintype "passive"))
      (node (ref "R2") (pin "2") (pinfunction "2_2") (pintype "passive"))
      (node (ref "R7") (pin "2") (pinfunction "2_2") (pintype "passive"))
      (node (ref "R8") (pin "2") (pinfunction "2_2") (pintype "passive"))
      (node (ref "R9") (pin "2") (pinfunction "2_2") (pintype "passive"))
      (node (ref "U1") (pin "1") (pinfunction "VBAT_1") (pintype "passive"))
      (node (ref "U1") (pin "19") (pinfunction "VDD_19") (pintype "passive"))
      (node (ref "U1") (pin "32") (pinfunction "VDD_32") (pintype "passive"))
      (node (ref "U1") (pin "48") (pinfunction "VDD_48") (pintype "passive"))
      (node (ref "U1") (pin "64") (pinfunction "VDD_64") (pintype "passive"))
      (node (ref "U2") (pin "4") (pinfunction "VDD_4") (pintype "passive"))
      (node (ref "U8") (pin "4") (pinfunction "NC_4") (pintype "passive"))
      (node (ref "U8") (pin "5") (pinfunction "VOUT_5") (pintype "passive"))
      (node (ref "X1") (pin "4") (pinfunction "VDD_4") (pintype "passive"))
    )
    (net (code "48") (name "3V3A") (class "Default")
      (node (ref "C13") (pin "2") (pinfunction "2_2") (pintype "passive"))
      (node (ref "C14") (pin "2") (pinfunction "2_2") (pintype "passive"))
      (node (ref "C15") (pin "2") (pinfunction "2_2") (pintype "passive"))
      (node (ref "C28") (pin "2") (pinfunction "2_2") (pintype "passive"))
      (node (ref "C8") (pin "2") (pinfunction "2_2") (pintype "passive"))
      (node (ref "R20") (pin "2") (pinfunction "2_2") (pintype "passive"))
      (node (ref "U1") (pin "13") (pinfunction "VDDA_13") (pintype "passive"))
      (node (ref "U4") (pin "3") (pinfunction "REF2_3") (pintype "passive"))
      (node (ref "U4") (pin "6") (pinfunction "VS_6") (pintype "passive"))
      (node (ref "U5") (pin "3") (pinfunction "REF2_3") (pintype "passive"))
      (node (ref "U5") (pin "6") (pinfunction "VS_6") (pintype "passive"))
      (node (ref "U6") (pin "3") (pinfunction "REF2_3") (pintype "passive"))
      (node (ref "U6") (pin "6") (pinfunction "VS_6") (pintype "passive"))
      (node (ref "U9") (pin "4") (pinfunction "NC_4") (pintype "passive"))
      (node (ref "U9") (pin "5") (pinfunction "VOUT_5") (pintype "passive"))
    )
    (net (code "49") (name "<NO NET>") (class "Default")
      (node (ref "C1") (pin "1") (pinfunction "1_1") (pintype "passive"))
      (node (ref "C10") (pin "1") (pinfunction "1_1") (pintype "passive"))
      (node (ref "C13") (pin "1") (pinfunction "1_1") (pintype "passive"))
      (node (ref "C14") (pin "1") (pinfunction "1_1") (pintype "passive"))
      (node (ref "C15") (pin "1") (pinfunction "1_1") (pintype "passive"))
      (node (ref "C17") (pin "1") (pinfunction "1_1") (pintype "passive"))
      (node (ref "C19") (pin "1") (pinfunction "1_1") (pintype "passive"))
      (node (ref "C2") (pin "2") (pinfunction "2_2") (pintype "passive"))
      (node (ref "C20") (pin "1") (pinfunction "1_1") (pintype "passive"))
      (node (ref "C21") (pin "1") (pinfunction "1_1") (pintype "passive"))
      (node (ref "C22") (pin "1") (pinfunction "1_1") (pintype "passive"))
      (node (ref "C24") (pin "1") (pinfunction "1_1") (pintype "passive"))
      (node (ref "C25") (pin "2") (pinfunction "2_2") (pintype "passive"))
      (node (ref "C26") (pin "1") (pinfunction "1_1") (pintype "passive"))
      (node (ref "C27") (pin "2") (pinfunction "2_2") (pintype "passive"))
      (node (ref "C28") (pin "1") (pinfunction "1_1") (pintype "passive"))
      (node (ref "C29") (pin "1") (pinfunction "1_1") (pintype "passive"))
      (node (ref "C3") (pin "2") (pinfunction "2_2") (pintype "passive"))
      (node (ref "C4") (pin "1") (pinfunction "1_1") (pintype "passive"))
      (node (ref "C5") (pin "1") (pinfunction "1_1") (pintype "passive"))
      (node (ref "C6") (pin "1") (pinfunction "1_1") (pintype "passive"))
      (node (ref "C7") (pin "1") (pinfunction "1_1") (pintype "passive"))
      (node (ref "C8") (pin "1") (pinfunction "1_1") (pintype "passive"))
      (node (ref "C9") (pin "1") (pinfunction "1_1") (pintype "passive"))
      (node (ref "CN2") (pin "2") (pinfunction "2_2") (pintype "passive"))
      (node (ref "D1") (pin "2") (pinfunction "A_2") (pintype "passive"))
      (node (ref "D4") (pin "1") (pinfunction "1_1") (pintype "passive"))
      (node (ref "D5") (pin "2") (pinfunction "2_2") (pintype "passive"))
      (node (ref "H1") (pin "4") (pinfunction "4_4") (pintype "passive"))
      (node (ref "H2") (pin "2") (pinfunction "2_2") (pintype "passive"))
      (node (ref "LED1") (pin "1") (pinfunction "-_1") (pintype "passive"))
      (node (ref "LED2") (pin "1") (pinfunction "-_1") (pintype "passive"))
      (node (ref "LED3") (pin "1") (pinfunction "-_1") (pintype "passive"))
      (node (ref "LED4") (pin "1") (pinfunction "C_1") (pintype "passive"))
      (node (ref "LED5") (pin "1") (pinfunction "C_1") (pintype "passive"))
      (node (ref "R1") (pin "2") (pinfunction "2_2") (pintype "passive"))
      (node (ref "R15") (pin "1") (pinfunction "1_1") (pintype "passive"))
      (node (ref "R17") (pin "2") (pinfunction "2_2") (pintype "passive"))
      (node (ref "R21") (pin "1") (pinfunction "1_1") (pintype "passive"))
      (node (ref "R21") (pin "2") (pinfunction "2_2") (pintype "passive"))
      (node (ref "R4") (pin "1") (pinfunction "1_1") (pintype "passive"))
      (node (ref "SW1") (pin "1") (pinfunction "1_1") (pintype "passive"))
      (node (ref "SW1") (pin "3") (pinfunction "3_3") (pintype "passive"))
      (node (ref "SW2") (pin "1") (pinfunction "1_1") (pintype "passive"))
      (node (ref "SW3") (pin "1") (pinfunction "1_1") (pintype "passive"))
      (node (ref "SW3") (pin "3") (pinfunction "3_3") (pintype "passive"))
      (node (ref "SW4") (pin "1") (pinfunction "1_1") (pintype "passive"))
      (node (ref "SW4") (pin "3") (pinfunction "3_3") (pintype "passive"))
      (node (ref "U1") (pin "12") (pinfunction "VSSA_12") (pintype "passive"))
      (node (ref "U1") (pin "18") (pinfunction "VSS_18") (pintype "passive"))
      (node (ref "U1") (pin "63") (pinfunction "VSS_63") (pintype "passive"))
      (node (ref "U10") (pin "4") (pinfunction "4_4") (pintype "passive"))
      (node (ref "U10") (pin "6") (pinfunction "6_6") (pintype "passive"))
      (node (ref "U2") (pin "1") (pinfunction "GND_1") (pintype "passive"))
      (node (ref "U2") (pin "12") (pinfunction "GND_12") (pintype "passive"))
      (node (ref "U2") (pin "2") (pinfunction "LEDK_2") (pintype "passive"))
      (node (ref "U2") (pin "5") (pinfunction "GND_5") (pintype "passive"))
      (node (ref "U2") (pin "6") (pinfunction "GND_6") (pintype "passive"))
      (node (ref "U3") (pin "10") (pinfunction "PGND3_10") (pintype "passive"))
      (node (ref "U3") (pin "12") (pinfunction "COMPP_12") (pintype "passive"))
      (node (ref "U3") (pin "13") (pinfunction "COMPN_13") (pintype "passive"))
      (node (ref "U3") (pin "14") (pinfunction "GND_14") (pintype "passive"))
      (node (ref "U3") (pin "20") (pinfunction "GND_20") (pintype "passive"))
      (node (ref "U3") (pin "28") (pinfunction "GND_28") (pintype "passive"))
      (node (ref "U3") (pin "29") (pinfunction "EP_29") (pintype "passive"))
      (node (ref "U3") (pin "6") (pinfunction "PGND1_6") (pintype "passive"))
      (node (ref "U3") (pin "7") (pinfunction "PGND2_7") (pintype "passive"))
      (node (ref "U4") (pin "2") (pinfunction "GND_2") (pintype "passive"))
      (node (ref "U4") (pin "4") (pinfunction "NC_4") (pintype "passive"))
      (node (ref "U4") (pin "7") (pinfunction "REF1_7") (pintype "passive"))
      (node (ref "U5") (pin "2") (pinfunction "GND_2") (pintype "passive"))
      (node (ref "U5") (pin "4") (pinfunction "NC_4") (pintype "passive"))
      (node (ref "U5") (pin "7") (pinfunction "REF1_7") (pintype "passive"))
      (node (ref "U6") (pin "2") (pinfunction "GND_2") (pintype "passive"))
      (node (ref "U6") (pin "4") (pinfunction "NC_4") (pintype "passive"))
      (node (ref "U6") (pin "7") (pinfunction "REF1_7") (pintype "passive"))
      (node (ref "U7") (pin "2") (pinfunction "GND_2") (pintype "passive"))
      (node (ref "U8") (pin "2") (pinfunction "GND_2") (pintype "passive"))
      (node (ref "U9") (pin "2") (pinfunction "GND_2") (pintype "passive"))
      (node (ref "USBC1") (pin "0") (pinfunction "SH_0") (pintype "passive"))
      (node (ref "USBC1") (pin "1") (pinfunction "SH_1") (pintype "passive"))
      (node (ref "USBC1") (pin "2") (pinfunction "SH_2") (pintype "passive"))
      (node (ref "USBC1") (pin "3") (pinfunction "SH_3") (pintype "passive"))
      (node (ref "USBC1") (pin "A1") (pinfunction "GND_A1") (pintype "passive"))
      (node (ref "USBC1") (pin "A12") (pinfunction "GND_A12") (pintype "passive"))
      (node (ref "USBC1") (pin "B1") (pinfunction "GND_B1") (pintype "passive"))
      (node (ref "USBC1") (pin "B12") (pinfunction "GND_B12") (pintype "passive"))
      (node (ref "X1") (pin "2") (pinfunction "GND_2") (pintype "passive"))
    )
    (net (code "50") (name "Net-(D1-C)") (class "Default")
      (node (ref "C16") (pin "1") (pinfunction "1_1") (pintype "passive"))
      (node (ref "D1") (pin "1") (pinfunction "C_1") (pintype "passive"))
      (node (ref "L1") (pin "1") (pinfunction "1_1") (pintype "passive"))
      (node (ref "U7") (pin "6") (pinfunction "SW_6") (pintype "passive"))
    )
    (net (code "51") (name "Net-(LED1-+)") (class "Default")
      (node (ref "LED1") (pin "2") (pinfunction "+_2") (pintype "passive"))
      (node (ref "R18") (pin "1") (pinfunction "1_1") (pintype "passive"))
    )
    (net (code "52") (name "Net-(LED2-+)") (class "Default")
      (node (ref "LED2") (pin "2") (pinfunction "+_2") (pintype "passive"))
      (node (ref "R19") (pin "1") (pinfunction "1_1") (pintype "passive"))
    )
    (net (code "53") (name "Net-(LED3-+)") (class "Default")
      (node (ref "LED3") (pin "2") (pinfunction "+_2") (pintype "passive"))
      (node (ref "R20") (pin "1") (pinfunction "1_1") (pintype "passive"))
    )
    (net (code "54") (name "Net-(LED4-A)") (class "Default")
      (node (ref "LED4") (pin "2") (pinfunction "A_2") (pintype "passive"))
      (node (ref "R22") (pin "2") (pinfunction "2_2") (pintype "passive"))
    )
    (net (code "55") (name "Net-(LED5-A)") (class "Default")
      (node (ref "LED5") (pin "2") (pinfunction "A_2") (pintype "passive"))
      (node (ref "R23") (pin "2") (pinfunction "2_2") (pintype "passive"))
    )
    (net (code "56") (name "Net-(U1A-BOOT0)") (class "Default")
      (node (ref "R1") (pin "1") (pinfunction "1_1") (pintype "passive"))
      (node (ref "U1") (pin "60") (pinfunction "BOOT0_60") (pintype "passive"))
    )
    (net (code "57") (name "Net-(U1A-PH0-OSC_IN(PH0))") (class "Default")
      (node (ref "U1") (pin "5") (pinfunction "PH0-OSC_IN(PH0)_5") (pintype "passive"))
      (node (ref "X1") (pin "3") (pinfunction "OUTPUT_3") (pintype "passive"))
    )
    (net (code "58") (name "Net-(U1A-VCAP_1)") (class "Default")
      (node (ref "C3") (pin "1") (pinfunction "1_1") (pintype "passive"))
      (node (ref "U1") (pin "31") (pinfunction "VCAP_1_31") (pintype "passive"))
    )
    (net (code "59") (name "Net-(U1A-VCAP_2)") (class "Default")
      (node (ref "C2") (pin "1") (pinfunction "1_1") (pintype "passive"))
      (node (ref "U1") (pin "47") (pinfunction "VCAP_2_47") (pintype "passive"))
    )
    (net (code "60") (name "Net-(U3-CP1)") (class "Default")
      (node (ref "C11") (pin "2") (pinfunction "2_2") (pintype "passive"))
      (node (ref "U3") (pin "1") (pinfunction "CP1_1") (pintype "passive"))
    )
    (net (code "61") (name "Net-(U3-CP2)") (class "Default")
      (node (ref "C11") (pin "1") (pinfunction "1_1") (pintype "passive"))
      (node (ref "U3") (pin "2") (pinfunction "CP2_2") (pintype "passive"))
    )
    (net (code "62") (name "Net-(U3-FAULT#)") (class "Default")
      (node (ref "R10") (pin "1") (pinfunction "1_1") (pintype "passive"))
      (node (ref "U3") (pin "18") (pinfunction "FAULT#_18") (pintype "passive"))
    )
    (net (code "63") (name "Net-(U3-VCP)") (class "Default")
      (node (ref "C12") (pin "2") (pinfunction "2_2") (pintype "passive"))
      (node (ref "U3") (pin "3") (pinfunction "VCP_3") (pintype "passive"))
    )
    (net (code "64") (name "Net-(U7-BST)") (class "Default")
      (node (ref "C16") (pin "2") (pinfunction "2_2") (pintype "passive"))
      (node (ref "U7") (pin "1") (pinfunction "BST_1") (pintype "passive"))
    )
    (net (code "65") (name "Net-(U7-EN)") (class "Default")
      (node (ref "R16") (pin "1") (pinfunction "1_1") (pintype "passive"))
      (node (ref "R17") (pin "1") (pinfunction "1_1") (pintype "passive"))
      (node (ref "U7") (pin "4") (pinfunction "EN_4") (pintype "passive"))
    )
    (net (code "66") (name "Net-(U7-FB)") (class "Default")
      (node (ref "C18") (pin "1") (pinfunction "1_1") (pintype "passive"))
      (node (ref "R14") (pin "1") (pinfunction "1_1") (pintype "passive"))
      (node (ref "R15") (pin "2") (pinfunction "2_2") (pintype "passive"))
      (node (ref "U7") (pin "3") (pinfunction "FB_3") (pintype "passive"))
    )
    (net (code "67") (name "Net-(USBC1-DN1)") (class "Default")
      (node (ref "R5") (pin "1") (pinfunction "1_1") (pintype "passive"))
      (node (ref "USBC1") (pin "A7") (pinfunction "DN1_A7") (pintype "passive"))
      (node (ref "USBC1") (pin "B7") (pinfunction "DN2_B7") (pintype "passive"))
    )
    (net (code "68") (name "Net-(USBC1-DP1)") (class "Default")
      (node (ref "R6") (pin "1") (pinfunction "1_1") (pintype "passive"))
      (node (ref "USBC1") (pin "A6") (pinfunction "DP1_A6") (pintype "passive"))
      (node (ref "USBC1") (pin "B6") (pinfunction "DP2_B6") (pintype "passive"))
    )
    (net (code "69") (name "PVDD") (class "Default")
      (node (ref "C12") (pin "1") (pinfunction "1_1") (pintype "passive"))
      (node (ref "C19") (pin "2") (pinfunction "2_2") (pintype "passive"))
      (node (ref "C20") (pin "2") (pinfunction "2_2") (pintype "passive"))
      (node (ref "C21") (pin "2") (pinfunction "2_2") (pintype "passive"))
      (node (ref "C22") (pin "2") (pinfunction "2_2") (pintype "passive"))
      (node (ref "C24") (pin "2") (pinfunction "2_2") (pintype "passive"))
      (node (ref "C29") (pin "2") (pinfunction "2_2") (pintype "passive"))
      (node (ref "D2") (pin "1") (pinfunction "1_1") (pintype "passive"))
      (node (ref "D4") (pin "2") (pinfunction "2_2") (pintype "passive"))
      (node (ref "R16") (pin "2") (pinfunction "2_2") (pintype "passive"))
      (node (ref "R3") (pin "2") (pinfunction "2_2") (pintype "passive"))
      (node (ref "U3") (pin "11") (pinfunction "VM_11") (pintype "passive"))
      (node (ref "U3") (pin "4") (pinfunction "VM_4") (pintype "passive"))
      (node (ref "U7") (pin "5") (pinfunction "VIN_5") (pintype "passive"))
    )
    (net (code "70") (name "VBAT") (class "Default")
      (node (ref "CN2") (pin "1") (pinfunction "1_1") (pintype "passive"))
      (node (ref "D2") (pin "2") (pinfunction "2_2") (pintype "passive"))
    )
    (net (code "71") (name "unconnected-(CN2-Pad3)") (class "Default")
      (node (ref "CN2") (pin "3") (pinfunction "3_3") (pintype "passive+no_connect"))
    )
    (net (code "72") (name "unconnected-(CN2-Pad4)") (class "Default")
      (node (ref "CN2") (pin "4") (pinfunction "4_4") (pintype "passive+no_connect"))
    )
    (net (code "73") (name "unconnected-(SW5-Pad1)") (class "Default")
      (node (ref "SW5") (pin "1") (pinfunction "1_1") (pintype "passive"))
    )
    (net (code "74") (name "unconnected-(SW5-Pad2)") (class "Default")
      (node (ref "SW5") (pin "2") (pinfunction "2_2") (pintype "passive"))
    )
    (net (code "75") (name "unconnected-(SW5-Pad3)") (class "Default")
      (node (ref "SW5") (pin "3") (pinfunction "3_3") (pintype "passive"))
    )
    (net (code "76") (name "unconnected-(U1A-PA3-Pad17)") (class "Default")
      (node (ref "U1") (pin "17") (pinfunction "PA3_17") (pintype "passive+no_connect"))
    )
    (net (code "77") (name "unconnected-(U1A-PB1-Pad27)") (class "Default")
      (node (ref "U1") (pin "27") (pinfunction "PB1_27") (pintype "passive+no_connect"))
    )
    (net (code "78") (name "unconnected-(U1A-PB2-BOOT1(PB2)-Pad28)") (class "Default")
      (node (ref "U1") (pin "28") (pinfunction "PB2-BOOT1(PB2)_28") (pintype "passive+no_connect"))
    )
    (net (code "79") (name "unconnected-(U1A-PB4(NJTRST)-Pad56)") (class "Default")
      (node (ref "U1") (pin "56") (pinfunction "PB4(NJTRST)_56") (pintype "passive+no_connect"))
    )
    (net (code "80") (name "unconnected-(U1A-PB8-Pad61)") (class "Default")
      (node (ref "U1") (pin "61") (pinfunction "PB8_61") (pintype "passive+no_connect"))
    )
    (net (code "81") (name "unconnected-(U1A-PB9-Pad62)") (class "Default")
      (node (ref "U1") (pin "62") (pinfunction "PB9_62") (pintype "passive+no_connect"))
    )
    (net (code "82") (name "unconnected-(U1A-PB10-Pad29)") (class "Default")
      (node (ref "U1") (pin "29") (pinfunction "PB10_29") (pintype "passive+no_connect"))
    )
    (net (code "83") (name "unconnected-(U1A-PB11-Pad30)") (class "Default")
      (node (ref "U1") (pin "30") (pinfunction "PB11_30") (pintype "passive+no_connect"))
    )
    (net (code "84") (name "unconnected-(U1A-PC0-Pad8)") (class "Default")
      (node (ref "U1") (pin "8") (pinfunction "PC0_8") (pintype "passive+no_connect"))
    )
    (net (code "85") (name "unconnected-(U1A-PC1-Pad9)") (class "Default")
      (node (ref "U1") (pin "9") (pinfunction "PC1_9") (pintype "passive+no_connect"))
    )
    (net (code "86") (name "unconnected-(U1A-PC2-Pad10)") (class "Default")
      (node (ref "U1") (pin "10") (pinfunction "PC2_10") (pintype "passive+no_connect"))
    )
    (net (code "87") (name "unconnected-(U1A-PC3-Pad11)") (class "Default")
      (node (ref "U1") (pin "11") (pinfunction "PC3_11") (pintype "passive+no_connect"))
    )
    (net (code "88") (name "unconnected-(U1A-PH1-OSC_OUT(PH1)-Pad6)") (class "Default")
      (node (ref "U1") (pin "6") (pinfunction "PH1-OSC_OUT(PH1)_6") (pintype "passive+no_connect"))
    )
    (net (code "89") (name "unconnected-(U3-COMPO#-Pad19)") (class "Default")
      (node (ref "U3") (pin "19") (pinfunction "COMPO#_19") (pintype "passive+no_connect"))
    )
    (net (code "90") (name "unconnected-(U3-NC-Pad21)") (class "Default")
      (node (ref "U3") (pin "21") (pinfunction "NC_21") (pintype "passive+no_connect"))
    )
    (net (code "91") (name "unconnected-(U10-Pad5)") (class "Default")
      (node (ref "U10") (pin "5") (pinfunction "5_5") (pintype "passive+no_connect"))
    )
    (net (code "92") (name "unconnected-(U11-Pad5)") (class "Default")
      (node (ref "U11") (pin "5") (pinfunction "5_5") (pintype "passive+no_connect"))
    )
    (net (code "93") (name "unconnected-(U11-Pad6)") (class "Default")
      (node (ref "U11") (pin "6") (pinfunction "6_6") (pintype "passive+no_connect"))
    )
    (net (code "94") (name "unconnected-(U12-Pad5)") (class "Default")
      (node (ref "U12") (pin "5") (pinfunction "5_5") (pintype "passive+no_connect"))
    )
    (net (code "95") (name "unconnected-(U12-Pad6)") (class "Default")
      (node (ref "U12") (pin "6") (pinfunction "6_6") (pintype "passive+no_connect"))
    )
    (net (code "96") (name "unconnected-(USBC1-CC1-PadA5)") (class "Default")
      (node (ref "USBC1") (pin "A5") (pinfunction "CC1_A5") (pintype "passive+no_connect"))
    )
    (net (code "97") (name "unconnected-(USBC1-CC2-PadB5)") (class "Default")
      (node (ref "USBC1") (pin "B5") (pinfunction "CC2_B5") (pintype "passive+no_connect"))
    )
    (net (code "98") (name "unconnected-(USBC1-SBU1-PadA8)") (class "Default")
      (node (ref "USBC1") (pin "A8") (pinfunction "SBU1_A8") (pintype "passive+no_connect"))
    )
    (net (code "99") (name "unconnected-(USBC1-SBU2-PadB8)") (class "Default")
      (node (ref "USBC1") (pin "B8") (pinfunction "SBU2_B8") (pintype "passive+no_connect"))
    )
    (net (code "100") (name "unconnected-(USBC1-VBUS-PadA4)") (class "Default")
      (node (ref "USBC1") (pin "A4") (pinfunction "VBUS_A4") (pintype "passive+no_connect"))
    )
    (net (code "101") (name "unconnected-(USBC1-VBUS-PadA9)") (class "Default")
      (node (ref "USBC1") (pin "A9") (pinfunction "VBUS_A9") (pintype "passive+no_connect"))
    )
    (net (code "102") (name "unconnected-(USBC1-VBUS-PadB4)") (class "Default")
      (node (ref "USBC1") (pin "B4") (pinfunction "VBUS_B4") (pintype "passive+no_connect"))
    )
    (net (code "103") (name "unconnected-(USBC1-VBUS-PadB9)") (class "Default")
      (node (ref "USBC1") (pin "B9") (pinfunction "VBUS_B9") (pintype "passive+no_connect"))
    )
    (net (code "104") (name "unconnected-(X1-Tri-state-Pad1)") (class "Default")
      (node (ref "X1") (pin "1") (pinfunction "Tri-state_1") (pintype "passive+no_connect"))
    )
  )
)
